# board2.net
KiCad netlist of a schematic drawn in EAGLE
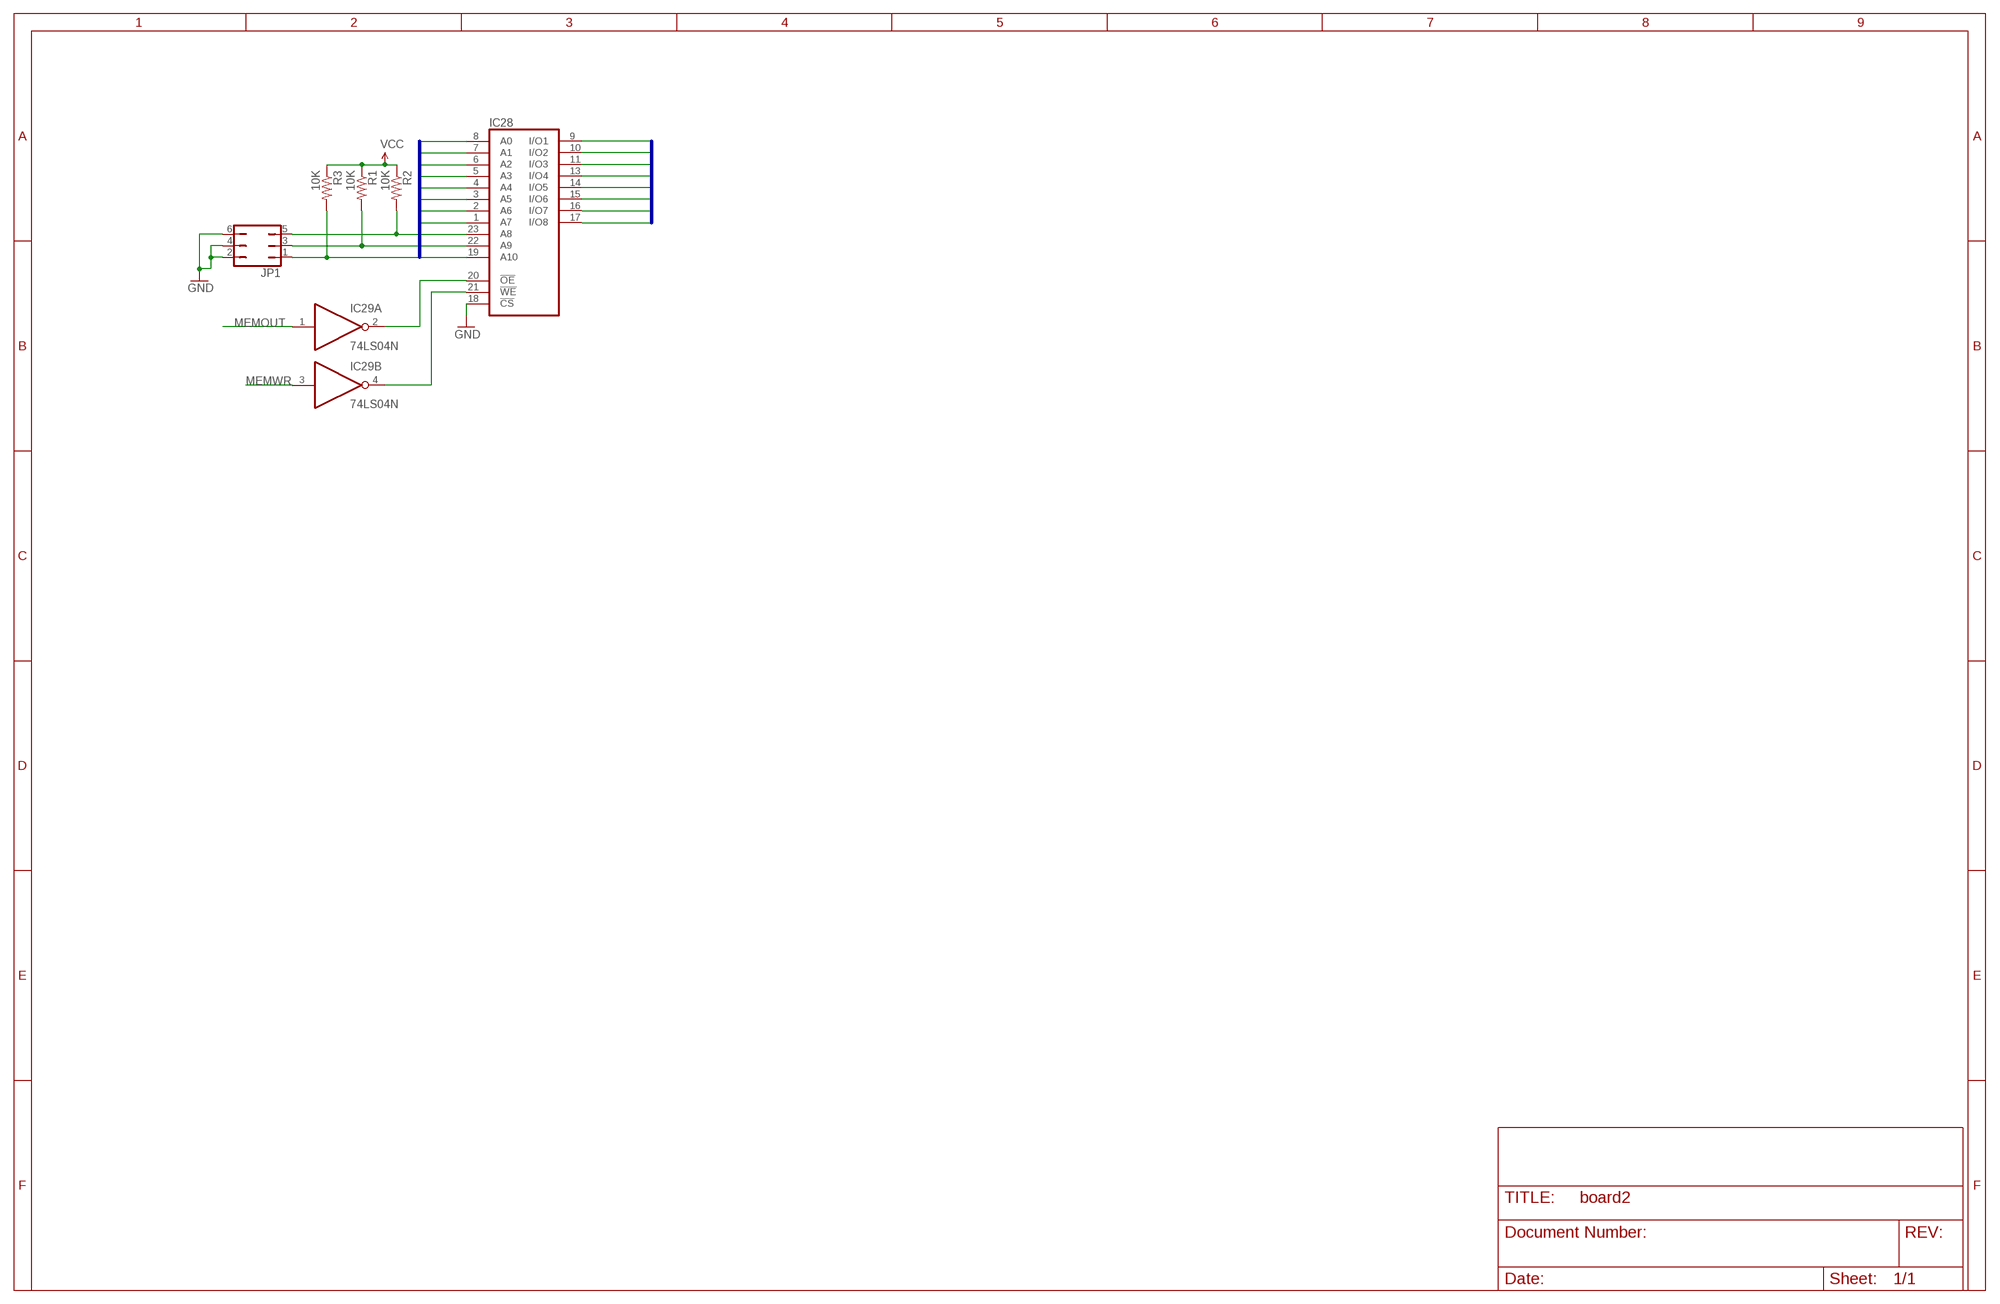
[diagram p0: schematic, sheet 1]

(export (version "E")
  (design (tool "Eeschema 10.0.6"))
  (components
    (comp (ref "IC28")
      (value "6116P")
      (footprint "eagle-import:DIL24-6")
      (libsource (lib "eagle-import") (part "6116P"))
    )
    (comp (ref "IC29")
      (value "74LS04N")
      (footprint "eagle-import:DIL14")
      (libsource (lib "eagle-import") (part "7404NLS"))
    )
    (comp (ref "JP1")
      (value "JP3Q")
      (footprint "eagle-import:JP3Q")
      (libsource (lib "eagle-import") (part "JP3Q"))
    )
    (comp (ref "R1")
      (value "10K")
      (footprint "eagle-import:0309_12")
      (libsource (lib "eagle-import") (part "R-US_0309/12"))
    )
    (comp (ref "R2")
      (value "10K")
      (footprint "eagle-import:0309_12")
      (libsource (lib "eagle-import") (part "R-US_0309/12"))
    )
    (comp (ref "R3")
      (value "10K")
      (footprint "eagle-import:0309_12")
      (libsource (lib "eagle-import") (part "R-US_0309/12"))
    )
  )
  (nets
    (net (code "1") (name "/MEMOUT") (class "Default")
      (node (ref "IC29") (pin "1") (pinfunction "I_1") (pintype "input"))
    )
    (net (code "2") (name "/MEMWR") (class "Default")
      (node (ref "IC29") (pin "3") (pinfunction "I_3") (pintype "input"))
    )
    (net (code "3") (name "GND") (class "Default")
      (node (ref "IC28") (pin "18") (pinfunction "~{CS}_18") (pintype "input"))
      (node (ref "JP1") (pin "2") (pinfunction "2_2") (pintype "passive"))
      (node (ref "JP1") (pin "4") (pinfunction "4_4") (pintype "passive"))
      (node (ref "JP1") (pin "6") (pinfunction "6_6") (pintype "passive"))
    )
    (net (code "4") (name "Net-(IC28A-A8)") (class "Default")
      (node (ref "IC28") (pin "23") (pinfunction "A8_23") (pintype "input"))
      (node (ref "JP1") (pin "5") (pinfunction "5_5") (pintype "passive"))
      (node (ref "R2") (pin "2") (pinfunction "2_2") (pintype "passive"))
    )
    (net (code "5") (name "Net-(IC28A-A9)") (class "Default")
      (node (ref "IC28") (pin "22") (pinfunction "A9_22") (pintype "input"))
      (node (ref "JP1") (pin "3") (pinfunction "3_3") (pintype "passive"))
      (node (ref "R1") (pin "2") (pinfunction "2_2") (pintype "passive"))
    )
    (net (code "6") (name "Net-(IC28A-A10)") (class "Default")
      (node (ref "IC28") (pin "19") (pinfunction "A10_19") (pintype "input"))
      (node (ref "JP1") (pin "1") (pinfunction "1_1") (pintype "passive"))
      (node (ref "R3") (pin "2") (pinfunction "2_2") (pintype "passive"))
    )
    (net (code "7") (name "Net-(IC28A-~{OE})") (class "Default")
      (node (ref "IC28") (pin "20") (pinfunction "~{OE}_20") (pintype "input"))
      (node (ref "IC29") (pin "2") (pinfunction "O_2") (pintype "output"))
    )
    (net (code "8") (name "Net-(IC28A-~{WE})") (class "Default")
      (node (ref "IC28") (pin "21") (pinfunction "~{WE}_21") (pintype "input"))
      (node (ref "IC29") (pin "4") (pinfunction "O_4") (pintype "output"))
    )
    (net (code "9") (name "VCC") (class "Default")
      (node (ref "R1") (pin "1") (pinfunction "1_1") (pintype "passive"))
      (node (ref "R2") (pin "1") (pinfunction "1_1") (pintype "passive"))
      (node (ref "R3") (pin "1") (pinfunction "1_1") (pintype "passive"))
    )
    (net (code "10") (name "unconnected-(IC28A-A0-Pad8)") (class "Default")
      (node (ref "IC28") (pin "8") (pinfunction "A0_8") (pintype "input"))
    )
    (net (code "11") (name "unconnected-(IC28A-A1-Pad7)") (class "Default")
      (node (ref "IC28") (pin "7") (pinfunction "A1_7") (pintype "input"))
    )
    (net (code "12") (name "unconnected-(IC28A-A2-Pad6)") (class "Default")
      (node (ref "IC28") (pin "6") (pinfunction "A2_6") (pintype "input"))
    )
    (net (code "13") (name "unconnected-(IC28A-A3-Pad5)") (class "Default")
      (node (ref "IC28") (pin "5") (pinfunction "A3_5") (pintype "input"))
    )
    (net (code "14") (name "unconnected-(IC28A-A4-Pad4)") (class "Default")
      (node (ref "IC28") (pin "4") (pinfunction "A4_4") (pintype "input"))
    )
    (net (code "15") (name "unconnected-(IC28A-A5-Pad3)") (class "Default")
      (node (ref "IC28") (pin "3") (pinfunction "A5_3") (pintype "input"))
    )
    (net (code "16") (name "unconnected-(IC28A-A6-Pad2)") (class "Default")
      (node (ref "IC28") (pin "2") (pinfunction "A6_2") (pintype "input"))
    )
    (net (code "17") (name "unconnected-(IC28A-A7-Pad1)") (class "Default")
      (node (ref "IC28") (pin "1") (pinfunction "A7_1") (pintype "input"))
    )
    (net (code "18") (name "unconnected-(IC28A-I{slash}O1-Pad9)") (class "Default")
      (node (ref "IC28") (pin "9") (pinfunction "I/O1_9") (pintype "bidirectional"))
    )
    (net (code "19") (name "unconnected-(IC28A-I{slash}O2-Pad10)") (class "Default")
      (node (ref "IC28") (pin "10") (pinfunction "I/O2_10") (pintype "bidirectional"))
    )
    (net (code "20") (name "unconnected-(IC28A-I{slash}O3-Pad11)") (class "Default")
      (node (ref "IC28") (pin "11") (pinfunction "I/O3_11") (pintype "bidirectional"))
    )
    (net (code "21") (name "unconnected-(IC28A-I{slash}O4-Pad13)") (class "Default")
      (node (ref "IC28") (pin "13") (pinfunction "I/O4_13") (pintype "bidirectional"))
    )
    (net (code "22") (name "unconnected-(IC28A-I{slash}O5-Pad14)") (class "Default")
      (node (ref "IC28") (pin "14") (pinfunction "I/O5_14") (pintype "bidirectional"))
    )
    (net (code "23") (name "unconnected-(IC28A-I{slash}O6-Pad15)") (class "Default")
      (node (ref "IC28") (pin "15") (pinfunction "I/O6_15") (pintype "bidirectional"))
    )
    (net (code "24") (name "unconnected-(IC28A-I{slash}O7-Pad16)") (class "Default")
      (node (ref "IC28") (pin "16") (pinfunction "I/O7_16") (pintype "bidirectional"))
    )
    (net (code "25") (name "unconnected-(IC28A-I{slash}O8-Pad17)") (class "Default")
      (node (ref "IC28") (pin "17") (pinfunction "I/O8_17") (pintype "bidirectional"))
    )
  )
)
